# Arduelli.net
KiCad netlist of a schematic drawn in EAGLE
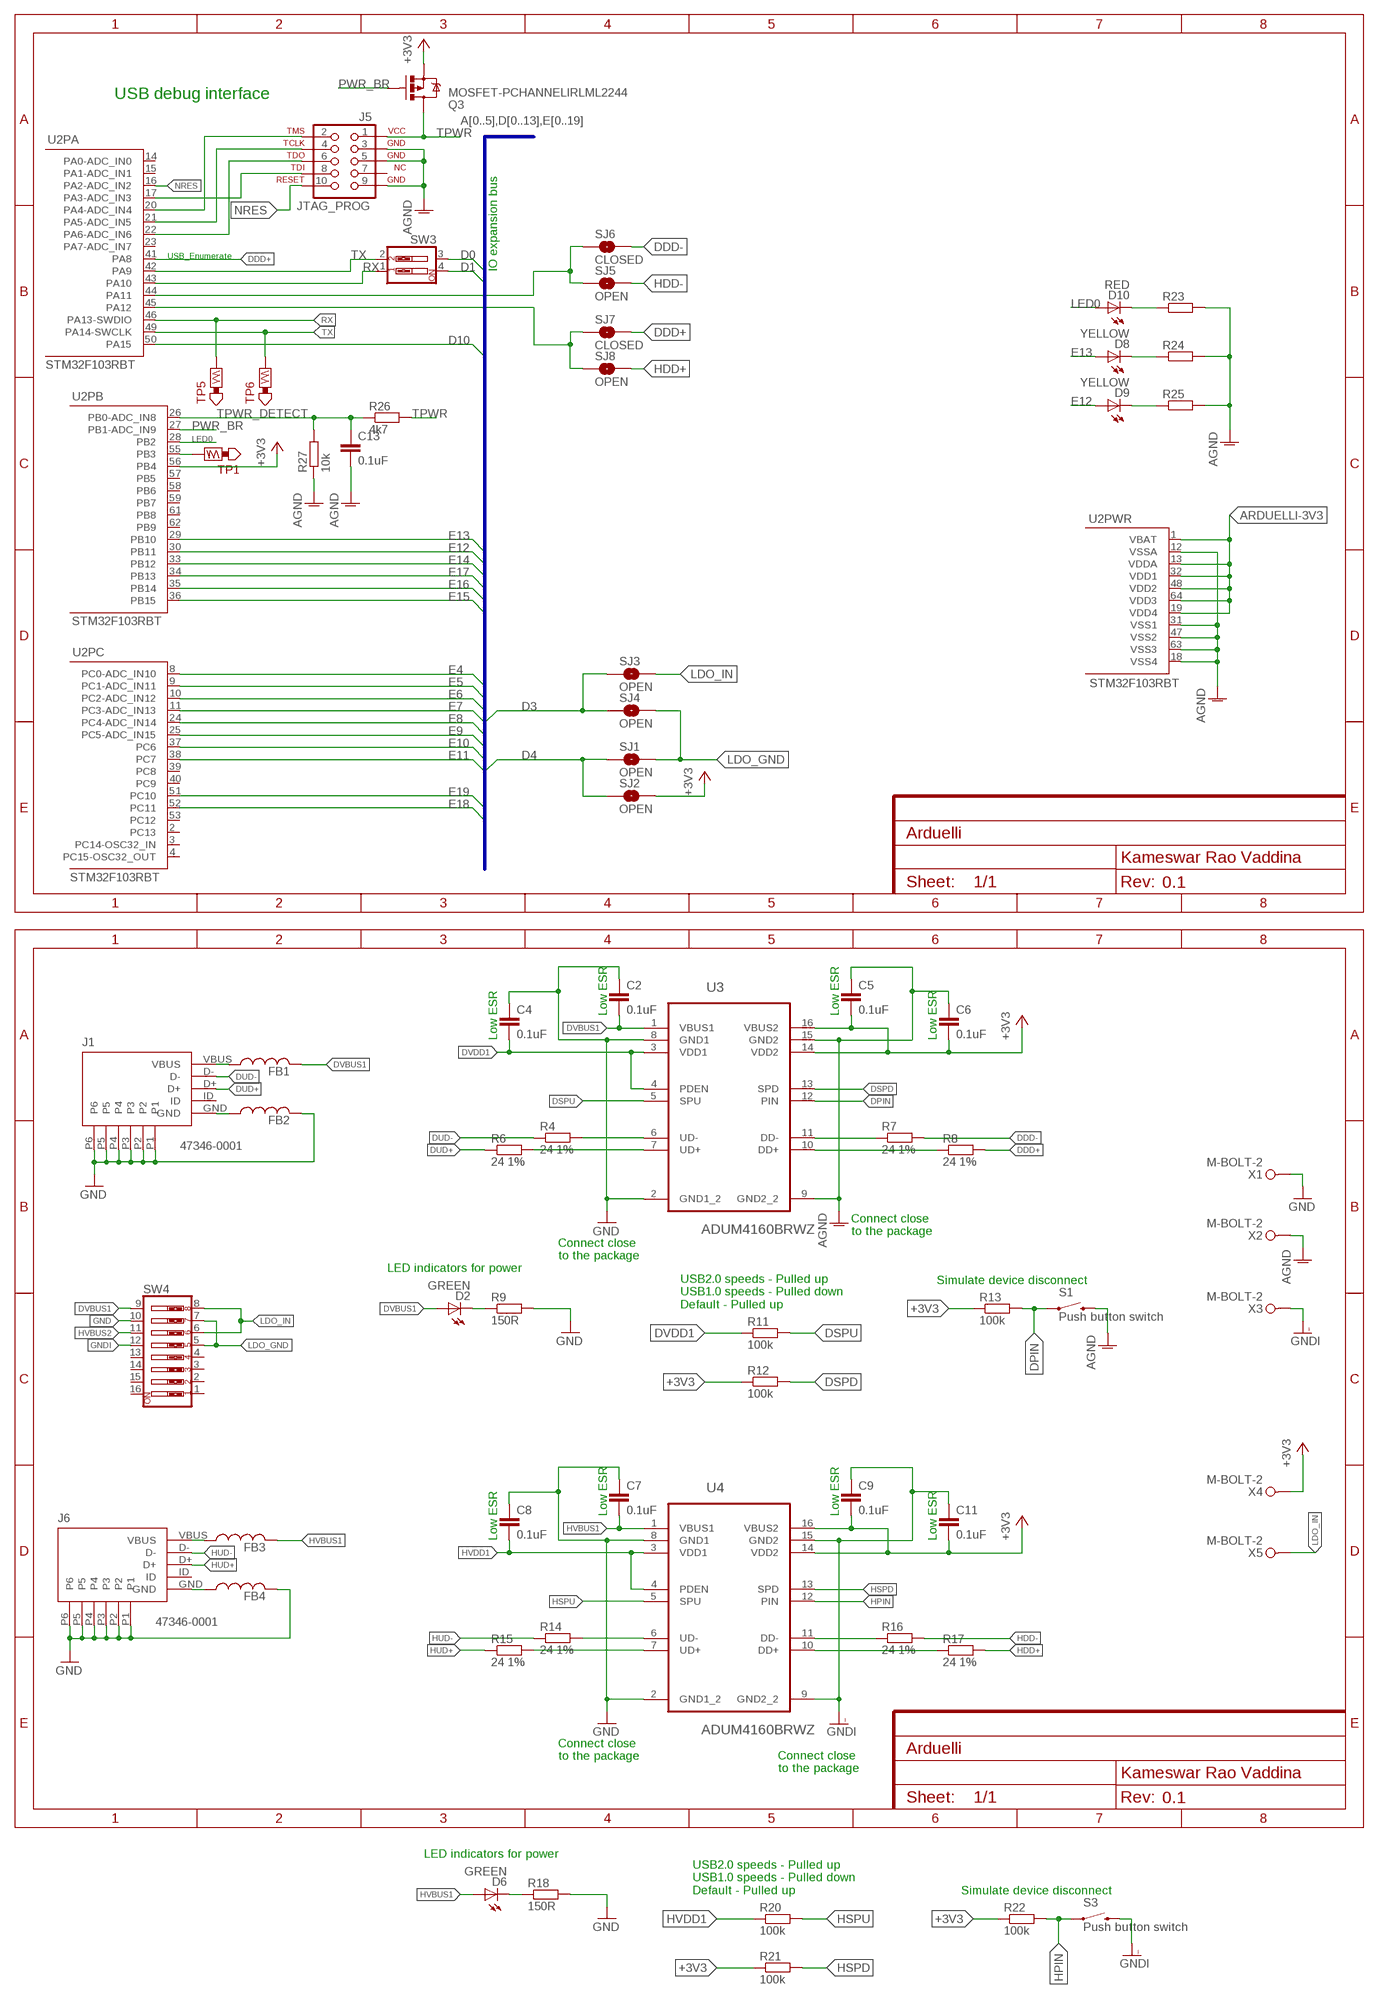
[diagram p0: schematic, sheet 1, part 1 of 2]
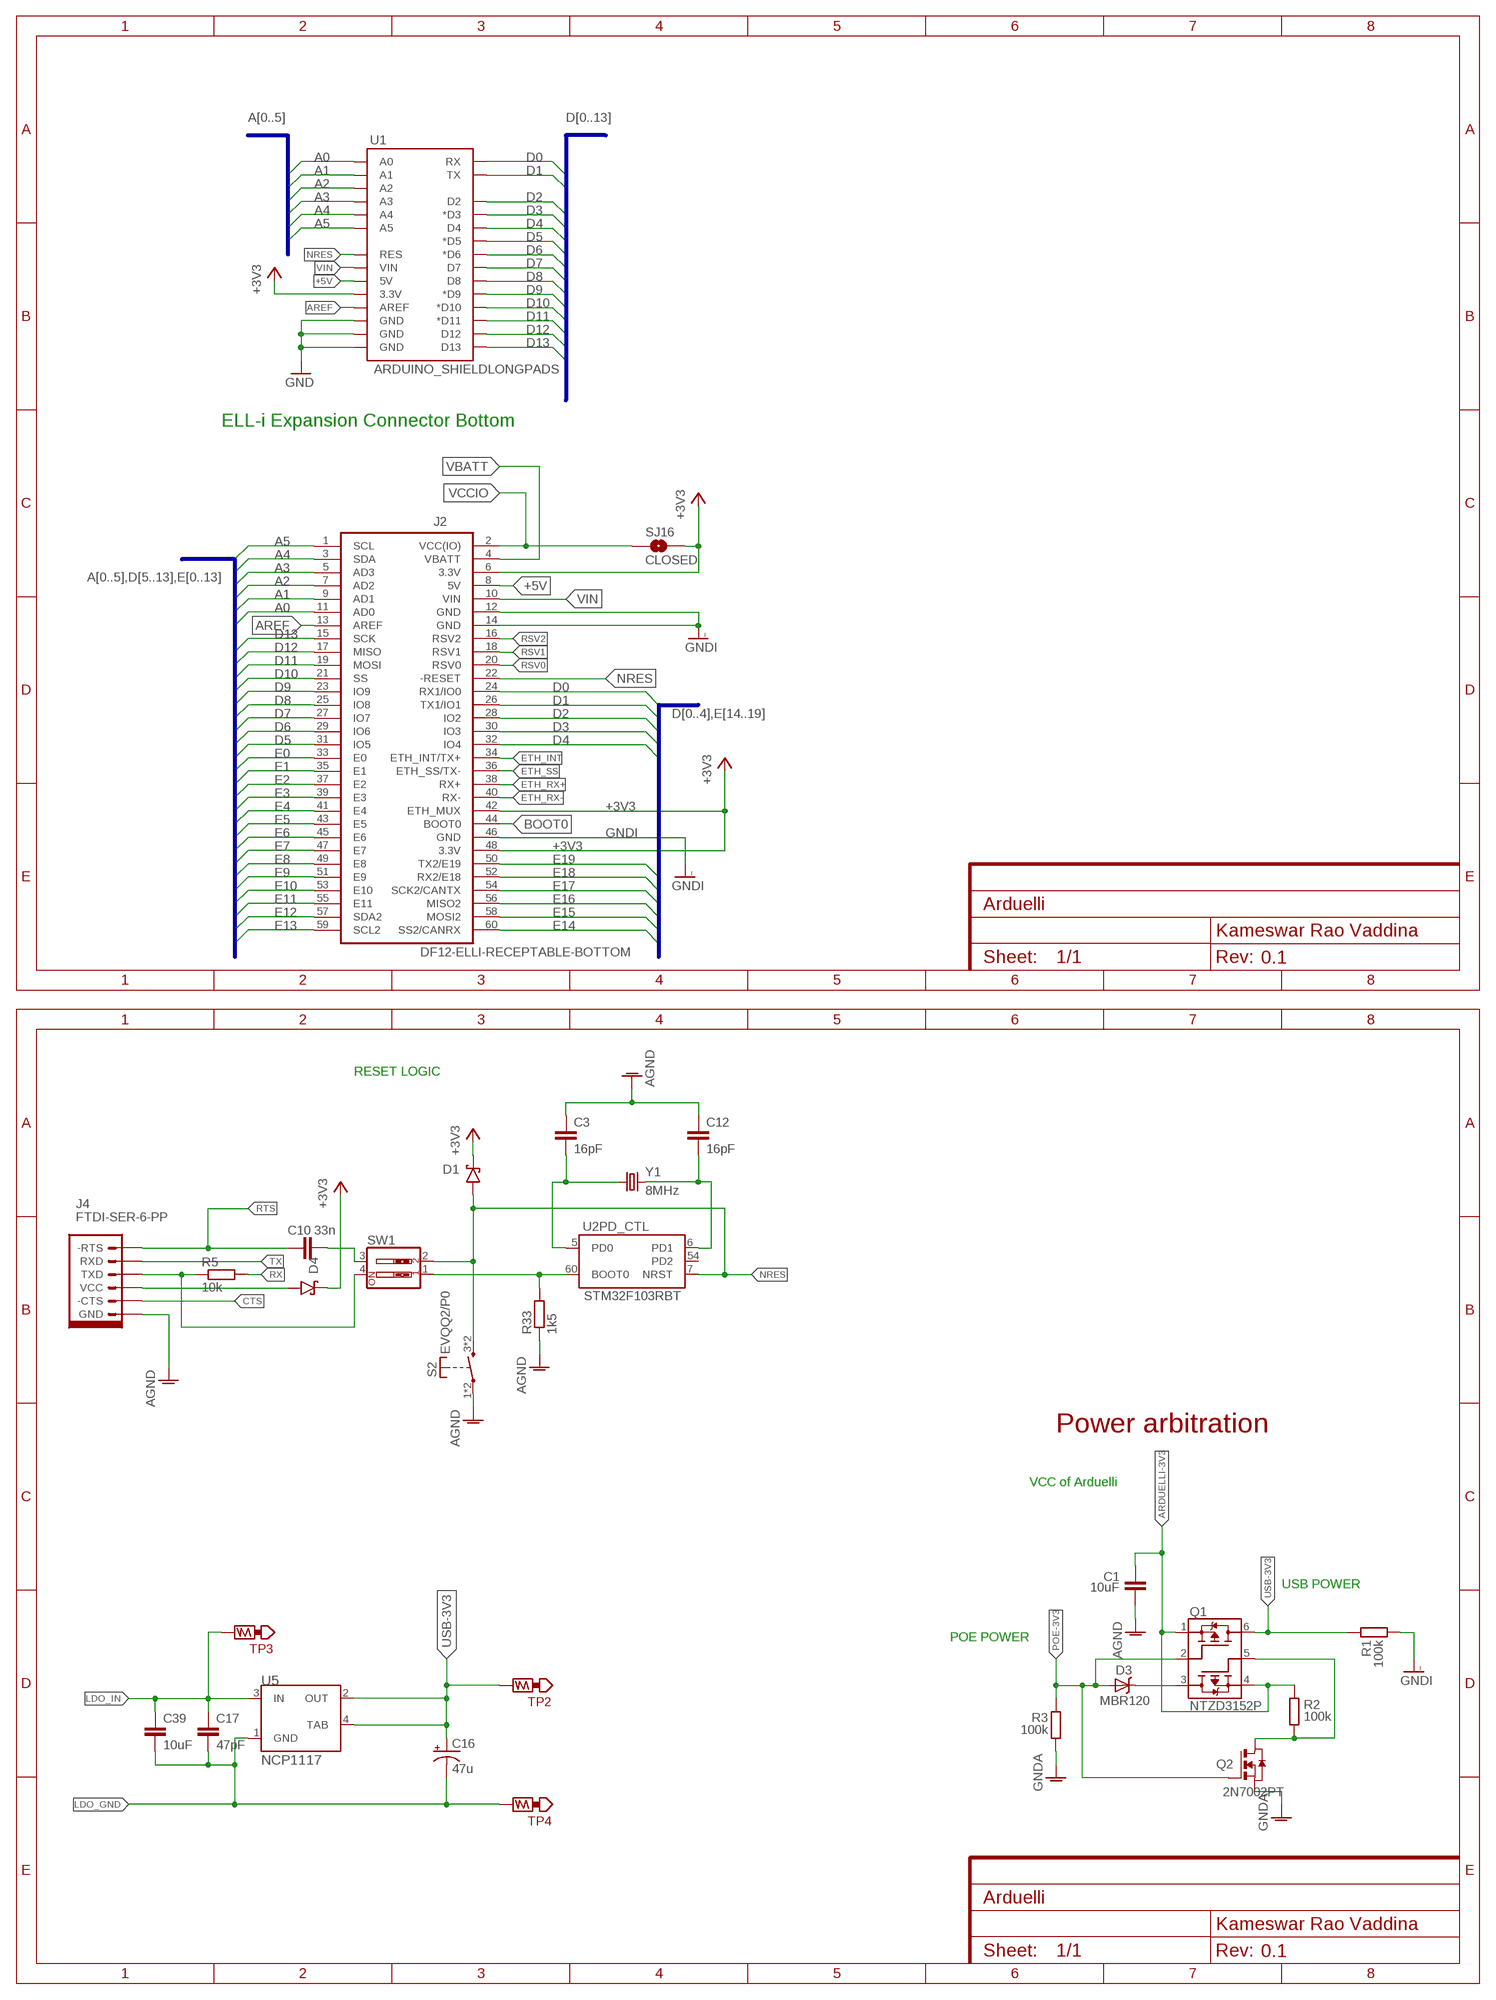
[diagram p1: schematic, sheet 1, part 2 of 2]

(export (version "E")
  (design (tool "Eeschema 10.0.6"))
  (components
    (comp (ref "C1")
      (value "10uF")
      (footprint "eagle-import:C0603")
      (libsource (lib "eagle-import") (part "C0603"))
    )
    (comp (ref "C2")
      (value "0.1uF")
      (footprint "eagle-import:C0402")
      (libsource (lib "eagle-import") (part "C0402"))
    )
    (comp (ref "C3")
      (value "16pF")
      (footprint "eagle-import:C0402")
      (libsource (lib "eagle-import") (part "C0402"))
    )
    (comp (ref "C4")
      (value "0.1uF")
      (footprint "eagle-import:C0402")
      (libsource (lib "eagle-import") (part "C0402"))
    )
    (comp (ref "C5")
      (value "0.1uF")
      (footprint "eagle-import:C0402")
      (libsource (lib "eagle-import") (part "C0402"))
    )
    (comp (ref "C6")
      (value "0.1uF")
      (footprint "eagle-import:C0402")
      (libsource (lib "eagle-import") (part "C0402"))
    )
    (comp (ref "C7")
      (value "0.1uF")
      (footprint "eagle-import:C0402")
      (libsource (lib "eagle-import") (part "C0402"))
    )
    (comp (ref "C8")
      (value "0.1uF")
      (footprint "eagle-import:C0402")
      (libsource (lib "eagle-import") (part "C0402"))
    )
    (comp (ref "C9")
      (value "0.1uF")
      (footprint "eagle-import:C0402")
      (libsource (lib "eagle-import") (part "C0402"))
    )
    (comp (ref "C10")
      (value "33n")
      (footprint "eagle-import:C0402")
      (libsource (lib "eagle-import") (part "C0402"))
    )
    (comp (ref "C11")
      (value "0.1uF")
      (footprint "eagle-import:C0402")
      (libsource (lib "eagle-import") (part "C0402"))
    )
    (comp (ref "C12")
      (value "16pF")
      (footprint "eagle-import:C0402")
      (libsource (lib "eagle-import") (part "C0402"))
    )
    (comp (ref "C13")
      (value "0.1uF")
      (footprint "eagle-import:C0402")
      (libsource (lib "eagle-import") (part "C0402"))
    )
    (comp (ref "C16")
      (value "47u")
      (footprint "eagle-import:CT6032")
      (libsource (lib "eagle-import") (part "CPOL6032"))
    )
    (comp (ref "C17")
      (value "47pF")
      (footprint "eagle-import:C0805")
      (libsource (lib "eagle-import") (part "C0805"))
    )
    (comp (ref "C39")
      (value "10uF")
      (footprint "eagle-import:C0805")
      (libsource (lib "eagle-import") (part "C0805"))
    )
    (comp (ref "D1")
      (value "BAT60J")
      (footprint "eagle-import:SOD323_DIODE")
      (libsource (lib "eagle-import") (part "BAT60J"))
    )
    (comp (ref "D2")
      (value "GREEN")
      (footprint "eagle-import:LED-0603")
      (libsource (lib "eagle-import") (part "LED-GREEN0603"))
    )
    (comp (ref "D3")
      (value "MBR120")
      (footprint "eagle-import:DIODE-B2100")
      (libsource (lib "eagle-import") (part "DIODE-SCHOTTKYB2100"))
    )
    (comp (ref "D4")
      (value "BAT60J")
      (footprint "eagle-import:SOD323_DIODE")
      (libsource (lib "eagle-import") (part "BAT60J"))
    )
    (comp (ref "D6")
      (value "GREEN")
      (footprint "eagle-import:LED-0603")
      (libsource (lib "eagle-import") (part "LED-GREEN0603"))
    )
    (comp (ref "D8")
      (value "YELLOW")
      (footprint "eagle-import:LED-0603")
      (libsource (lib "eagle-import") (part "LED-YELLOW0603"))
    )
    (comp (ref "D9")
      (value "YELLOW")
      (footprint "eagle-import:LED-0603")
      (libsource (lib "eagle-import") (part "LED-YELLOW0603"))
    )
    (comp (ref "D10")
      (value "RED")
      (footprint "eagle-import:LED-0603")
      (libsource (lib "eagle-import") (part "LED-RED0603"))
    )
    (comp (ref "FB1")
      (value "FB1206")
      (footprint "eagle-import:FB1206")
      (libsource (lib "eagle-import") (part "FB1206"))
    )
    (comp (ref "FB2")
      (value "FB1206")
      (footprint "eagle-import:FB1206")
      (libsource (lib "eagle-import") (part "FB1206"))
    )
    (comp (ref "FB3")
      (value "FB1206")
      (footprint "eagle-import:FB1206")
      (libsource (lib "eagle-import") (part "FB1206"))
    )
    (comp (ref "FB4")
      (value "FB1206")
      (footprint "eagle-import:FB1206")
      (libsource (lib "eagle-import") (part "FB1206"))
    )
    (comp (ref "J1")
      (value "47346-0001")
      (footprint "eagle-import:MICRO_USB")
      (fields (field (name "PARTNO") "AS-ITM-00021"))
      (libsource (lib "eagle-import") (part "MICRO-USB"))
    )
    (comp (ref "J2")
      (value "DF12-ELLI-RECEPTABLE-BOTTOM")
      (footprint "eagle-import:DF12-60DS-0.5V")
      (libsource (lib "eagle-import") (part "DF12-ELLI-RECEPTABLE-BOTTOM"))
    )
    (comp (ref "J4")
      (value "FTDI-SER-6-PP")
      (footprint "eagle-import:FTDI-SER-6-SIL")
      (libsource (lib "eagle-import") (part "FTDI-SER-6-PP"))
    )
    (comp (ref "J5")
      (value "JTAG_PROG")
      (footprint "eagle-import:CLP-105-02-X-D")
      (libsource (lib "eagle-import") (part "JTAG_PROG"))
    )
    (comp (ref "J6")
      (value "47346-0001")
      (footprint "eagle-import:MICRO_USB")
      (fields (field (name "PARTNO") "AS-ITM-00021"))
      (libsource (lib "eagle-import") (part "MICRO-USB"))
    )
    (comp (ref "Q1")
      (value "NTZD3152P")
      (footprint "eagle-import:SOT-563")
      (libsource (lib "eagle-import") (part "NTZD3152P"))
    )
    (comp (ref "Q2")
      (value "2N7002PT")
      (footprint "eagle-import:SOT-416")
      (libsource (lib "eagle-import") (part "2N7002PT"))
    )
    (comp (ref "Q3")
      (value "MOSFET-PCHANNELIRLML2244")
      (footprint "eagle-import:SOT23-3")
      (libsource (lib "eagle-import") (part "MOSFET-PCHANNELIRLML2244"))
    )
    (comp (ref "R1")
      (value "100k")
      (footprint "eagle-import:R0402")
      (libsource (lib "eagle-import") (part "R0402"))
    )
    (comp (ref "R2")
      (value "100k")
      (footprint "eagle-import:R0402")
      (libsource (lib "eagle-import") (part "R0402"))
    )
    (comp (ref "R3")
      (value "100k")
      (footprint "eagle-import:R0402")
      (libsource (lib "eagle-import") (part "R0402"))
    )
    (comp (ref "R4")
      (value "24 1%")
      (footprint "eagle-import:R0402")
      (libsource (lib "eagle-import") (part "R0402"))
    )
    (comp (ref "R5")
      (value "10k")
      (footprint "eagle-import:R0402")
      (libsource (lib "eagle-import") (part "R0402"))
    )
    (comp (ref "R6")
      (value "24 1%")
      (footprint "eagle-import:R0402")
      (libsource (lib "eagle-import") (part "R0402"))
    )
    (comp (ref "R7")
      (value "24 1%")
      (footprint "eagle-import:R0402")
      (libsource (lib "eagle-import") (part "R0402"))
    )
    (comp (ref "R8")
      (value "24 1%")
      (footprint "eagle-import:R0402")
      (libsource (lib "eagle-import") (part "R0402"))
    )
    (comp (ref "R9")
      (value "150R")
      (footprint "eagle-import:R0402")
      (libsource (lib "eagle-import") (part "R0402"))
    )
    (comp (ref "R11")
      (value "100k")
      (footprint "eagle-import:R0402")
      (libsource (lib "eagle-import") (part "R0402"))
    )
    (comp (ref "R12")
      (value "100k")
      (footprint "eagle-import:R0402")
      (libsource (lib "eagle-import") (part "R0402"))
    )
    (comp (ref "R13")
      (value "100k")
      (footprint "eagle-import:R0402")
      (libsource (lib "eagle-import") (part "R0402"))
    )
    (comp (ref "R14")
      (value "24 1%")
      (footprint "eagle-import:R0402")
      (libsource (lib "eagle-import") (part "R0402"))
    )
    (comp (ref "R15")
      (value "24 1%")
      (footprint "eagle-import:R0402")
      (libsource (lib "eagle-import") (part "R0402"))
    )
    (comp (ref "R16")
      (value "24 1%")
      (footprint "eagle-import:R0402")
      (libsource (lib "eagle-import") (part "R0402"))
    )
    (comp (ref "R17")
      (value "24 1%")
      (footprint "eagle-import:R0402")
      (libsource (lib "eagle-import") (part "R0402"))
    )
    (comp (ref "R18")
      (value "150R")
      (footprint "eagle-import:R0402")
      (libsource (lib "eagle-import") (part "R0402"))
    )
    (comp (ref "R20")
      (value "100k")
      (footprint "eagle-import:R0402")
      (libsource (lib "eagle-import") (part "R0402"))
    )
    (comp (ref "R21")
      (value "100k")
      (footprint "eagle-import:R0402")
      (libsource (lib "eagle-import") (part "R0402"))
    )
    (comp (ref "R22")
      (value "100k")
      (footprint "eagle-import:R0402")
      (libsource (lib "eagle-import") (part "R0402"))
    )
    (comp (ref "R23")
      (value "R0402")
      (footprint "eagle-import:R0402")
      (libsource (lib "eagle-import") (part "R0402"))
    )
    (comp (ref "R24")
      (value "R0402")
      (footprint "eagle-import:R0402")
      (libsource (lib "eagle-import") (part "R0402"))
    )
    (comp (ref "R25")
      (value "R0402")
      (footprint "eagle-import:R0402")
      (libsource (lib "eagle-import") (part "R0402"))
    )
    (comp (ref "R26")
      (value "4k7")
      (footprint "eagle-import:R0402")
      (libsource (lib "eagle-import") (part "R0402"))
    )
    (comp (ref "R27")
      (value "10k")
      (footprint "eagle-import:R0402")
      (libsource (lib "eagle-import") (part "R0402"))
    )
    (comp (ref "R33")
      (value "1k5")
      (footprint "eagle-import:R0402")
      (libsource (lib "eagle-import") (part "R0402"))
    )
    (comp (ref "S1")
      (value "Push button switch")
      (footprint "eagle-import:TACTILE_SWITCH_SMD")
      (libsource (lib "eagle-import") (part "SWITCH-MOMENTARY-2SMD"))
    )
    (comp (ref "S2")
      (value "EVQQ2/P0")
      (footprint "eagle-import:EVQQ2_P0")
      (libsource (lib "eagle-import") (part "EVQQ2/P0"))
    )
    (comp (ref "S3")
      (value "Push button switch")
      (footprint "eagle-import:TACTILE_SWITCH_SMD")
      (libsource (lib "eagle-import") (part "SWITCH-MOMENTARY-2SMD"))
    )
    (comp (ref "SJ1")
      (value "OPEN")
      (footprint "eagle-import:SJ_2S-NO")
      (libsource (lib "eagle-import") (part "SOLDERJUMPERNO"))
    )
    (comp (ref "SJ2")
      (value "OPEN")
      (footprint "eagle-import:SJ_2S-NO")
      (libsource (lib "eagle-import") (part "SOLDERJUMPERNO"))
    )
    (comp (ref "SJ3")
      (value "OPEN")
      (footprint "eagle-import:SJ_2S-NO")
      (libsource (lib "eagle-import") (part "SOLDERJUMPERNO"))
    )
    (comp (ref "SJ4")
      (value "OPEN")
      (footprint "eagle-import:SJ_2S-NO")
      (libsource (lib "eagle-import") (part "SOLDERJUMPERNO"))
    )
    (comp (ref "SJ5")
      (value "OPEN")
      (footprint "eagle-import:SJ_2S-NO")
      (libsource (lib "eagle-import") (part "SOLDERJUMPERNO"))
    )
    (comp (ref "SJ6")
      (value "CLOSED")
      (footprint "eagle-import:SJ_2S-NO")
      (libsource (lib "eagle-import") (part "SOLDERJUMPERNO"))
    )
    (comp (ref "SJ7")
      (value "CLOSED")
      (footprint "eagle-import:SJ_2S-NO")
      (libsource (lib "eagle-import") (part "SOLDERJUMPERNO"))
    )
    (comp (ref "SJ8")
      (value "OPEN")
      (footprint "eagle-import:SJ_2S-NO")
      (libsource (lib "eagle-import") (part "SOLDERJUMPERNO"))
    )
    (comp (ref "SJ16")
      (value "CLOSED")
      (footprint "eagle-import:SJ_2S-TRACE")
      (libsource (lib "eagle-import") (part "SOLDERJUMPERTRACE"))
    )
    (comp (ref "SW1")
      (value "SW_DIP-2-SMT-HALFSIZE")
      (footprint "eagle-import:DIPSWITCH-02-50MIL")
      (libsource (lib "eagle-import") (part "SW_DIP-2-SMT-HALFSIZE"))
    )
    (comp (ref "SW3")
      (value "SW_DIP-2-SMT-HALFSIZE")
      (footprint "eagle-import:DIPSWITCH-02-50MIL")
      (libsource (lib "eagle-import") (part "SW_DIP-2-SMT-HALFSIZE"))
    )
    (comp (ref "SW4")
      (value "SW_DIP-8-SMT-HALFSIZE")
      (footprint "eagle-import:DIPSWITCH-08-50MIL")
      (libsource (lib "eagle-import") (part "SW_DIP-8-SMT-HALFSIZE"))
    )
    (comp (ref "TP1")
      (value "TEST_POINT-5000")
      (footprint "eagle-import:TP_5021")
      (libsource (lib "eagle-import") (part "TEST_POINT-5000"))
    )
    (comp (ref "TP2")
      (value "TEST_POINT-5021")
      (footprint "eagle-import:TP_5000")
      (libsource (lib "eagle-import") (part "TEST_POINT-5021"))
    )
    (comp (ref "TP3")
      (value "TEST_POINT-5021")
      (footprint "eagle-import:TP_5000")
      (libsource (lib "eagle-import") (part "TEST_POINT-5021"))
    )
    (comp (ref "TP4")
      (value "TEST_POINT-5021")
      (footprint "eagle-import:TP_5000")
      (libsource (lib "eagle-import") (part "TEST_POINT-5021"))
    )
    (comp (ref "TP5")
      (value "TEST_POINT-5000")
      (footprint "eagle-import:TP_5021")
      (libsource (lib "eagle-import") (part "TEST_POINT-5000"))
    )
    (comp (ref "TP6")
      (value "TEST_POINT-5000")
      (footprint "eagle-import:TP_5021")
      (libsource (lib "eagle-import") (part "TEST_POINT-5000"))
    )
    (comp (ref "U1")
      (value "ARDUINO_SHIELDLONGPADS")
      (footprint "eagle-import:DUEMILANOVE_SHIELD_LONGPADS")
      (libsource (lib "eagle-import") (part "ARDUINO_SHIELDLONGPADS"))
    )
    (comp (ref "U2")
      (value "STM32F103RBT")
      (footprint "eagle-import:LQFP64")
      (libsource (lib "eagle-import") (part "STM32F103RTB"))
    )
    (comp (ref "U3")
      (value "ADUM4160BRWZ")
      (footprint "eagle-import:SOIC127P1032X265-16N")
      (libsource (lib "eagle-import") (part "ADUM4160BRWZ"))
    )
    (comp (ref "U4")
      (value "ADUM4160BRWZ")
      (footprint "eagle-import:SOIC127P1032X265-16N")
      (libsource (lib "eagle-import") (part "ADUM4160BRWZ"))
    )
    (comp (ref "U5")
      (value "NCP1117")
      (footprint "eagle-import:SOT223")
      (libsource (lib "eagle-import") (part "NCP1117"))
    )
    (comp (ref "X1")
      (value "M-BOLT-2")
      (footprint "eagle-import:M2-1")
      (libsource (lib "eagle-import") (part "M-BOLT-2"))
    )
    (comp (ref "X2")
      (value "M-BOLT-2")
      (footprint "eagle-import:M2-1")
      (libsource (lib "eagle-import") (part "M-BOLT-2"))
    )
    (comp (ref "X3")
      (value "M-BOLT-2")
      (footprint "eagle-import:M2-1")
      (libsource (lib "eagle-import") (part "M-BOLT-2"))
    )
    (comp (ref "X4")
      (value "M-BOLT-2")
      (footprint "eagle-import:M2-1")
      (libsource (lib "eagle-import") (part "M-BOLT-2"))
    )
    (comp (ref "X5")
      (value "M-BOLT-2")
      (footprint "eagle-import:M2-1")
      (libsource (lib "eagle-import") (part "M-BOLT-2"))
    )
    (comp (ref "Y1")
      (value "8MHz")
      (footprint "eagle-import:CRYSTAL-TXC-7A")
      (libsource (lib "eagle-import") (part "CRYSTALTXC-7A"))
    )
  )
  (nets
    (net (code "1") (name "+3V3") (class "Default")
      (node (ref "C11") (pin "2") (pinfunction "2_2") (pintype "passive"))
      (node (ref "C5") (pin "2") (pinfunction "2_2") (pintype "passive"))
      (node (ref "C6") (pin "2") (pinfunction "2_2") (pintype "passive"))
      (node (ref "C9") (pin "2") (pinfunction "2_2") (pintype "passive"))
      (node (ref "D1") (pin "1") (pinfunction "C_1") (pintype "passive"))
      (node (ref "D4") (pin "1") (pinfunction "C_1") (pintype "passive"))
      (node (ref "J2") (pin "42") (pinfunction "ETH_MUX_42") (pintype "bidirectional"))
      (node (ref "J2") (pin "48") (pinfunction "3.3V_48") (pintype "bidirectional"))
      (node (ref "J2") (pin "6") (pinfunction "3.3V_6") (pintype "power_in"))
      (node (ref "Q3") (pin "2") (pinfunction "S_2") (pintype "passive"))
      (node (ref "R12") (pin "1") (pinfunction "1_1") (pintype "passive"))
      (node (ref "R13") (pin "1") (pinfunction "1_1") (pintype "passive"))
      (node (ref "R21") (pin "1") (pinfunction "1_1") (pintype "passive"))
      (node (ref "R22") (pin "1") (pinfunction "1_1") (pintype "passive"))
      (node (ref "SJ16") (pin "2") (pinfunction "2_2") (pintype "passive"))
      (node (ref "SJ2") (pin "2") (pinfunction "2_2") (pintype "passive"))
      (node (ref "U1") (pin "3.3V") (pinfunction "3.3V_3.3V") (pintype "bidirectional"))
      (node (ref "U2") (pin "56") (pinfunction "PB4_56") (pintype "bidirectional"))
      (node (ref "U3") (pin "14") (pinfunction "VDD2_14") (pintype "power_in"))
      (node (ref "U3") (pin "16") (pinfunction "VBUS2_16") (pintype "power_in"))
      (node (ref "U4") (pin "14") (pinfunction "VDD2_14") (pintype "power_in"))
      (node (ref "U4") (pin "16") (pinfunction "VBUS2_16") (pintype "power_in"))
      (node (ref "X4") (pin "1") (pinfunction "KL1_1") (pintype "passive"))
    )
    (net (code "2") (name "+5V") (class "Default")
      (node (ref "J2") (pin "8") (pinfunction "5V_8") (pintype "power_in"))
      (node (ref "U1") (pin "5V") (pinfunction "5V_5V") (pintype "bidirectional"))
    )
    (net (code "3") (name "/A0") (class "Default")
      (node (ref "J2") (pin "11") (pinfunction "AD0_11") (pintype "passive"))
      (node (ref "U1") (pin "A0") (pinfunction "A0_A0") (pintype "bidirectional"))
    )
    (net (code "4") (name "/A1") (class "Default")
      (node (ref "J2") (pin "9") (pinfunction "AD1_9") (pintype "passive"))
      (node (ref "U1") (pin "A1") (pinfunction "A1_A1") (pintype "bidirectional"))
    )
    (net (code "5") (name "/A2") (class "Default")
      (node (ref "J2") (pin "7") (pinfunction "AD2_7") (pintype "passive"))
      (node (ref "U1") (pin "A2") (pinfunction "A2_A2") (pintype "bidirectional"))
    )
    (net (code "6") (name "/A3") (class "Default")
      (node (ref "J2") (pin "5") (pinfunction "AD3_5") (pintype "passive"))
      (node (ref "U1") (pin "A3") (pinfunction "A3_A3") (pintype "bidirectional"))
    )
    (net (code "7") (name "/A4") (class "Default")
      (node (ref "J2") (pin "3") (pinfunction "SDA_3") (pintype "bidirectional"))
      (node (ref "U1") (pin "A4") (pinfunction "A4_A4") (pintype "bidirectional"))
    )
    (net (code "8") (name "/A5") (class "Default")
      (node (ref "J2") (pin "1") (pinfunction "SCL_1") (pintype "bidirectional"))
      (node (ref "U1") (pin "A5") (pinfunction "A5_A5") (pintype "bidirectional"))
    )
    (net (code "10") (name "/D0") (class "Default")
      (node (ref "J2") (pin "24") (pinfunction "RX1/IO0_24") (pintype "bidirectional"))
      (node (ref "SW3") (pin "3") (pinfunction "3_3") (pintype "passive"))
      (node (ref "U1") (pin "RX") (pinfunction "RX_RX") (pintype "bidirectional"))
    )
    (net (code "11") (name "/D1") (class "Default")
      (node (ref "J2") (pin "26") (pinfunction "TX1/IO1_26") (pintype "bidirectional"))
      (node (ref "SW3") (pin "4") (pinfunction "4_4") (pintype "passive"))
      (node (ref "U1") (pin "TX") (pinfunction "TX_TX") (pintype "bidirectional"))
    )
    (net (code "12") (name "/D2") (class "Default")
      (node (ref "J2") (pin "28") (pinfunction "IO2_28") (pintype "bidirectional"))
      (node (ref "U1") (pin "D2") (pinfunction "D2_D2") (pintype "bidirectional"))
    )
    (net (code "13") (name "/D3") (class "Default")
      (node (ref "J2") (pin "30") (pinfunction "IO3_30") (pintype "bidirectional"))
      (node (ref "SJ3") (pin "1") (pinfunction "1_1") (pintype "passive"))
      (node (ref "SJ4") (pin "1") (pinfunction "1_1") (pintype "passive"))
      (node (ref "U1") (pin "D3") (pinfunction "*D3_D3") (pintype "bidirectional"))
    )
    (net (code "14") (name "/D4") (class "Default")
      (node (ref "J2") (pin "32") (pinfunction "IO4_32") (pintype "bidirectional"))
      (node (ref "SJ1") (pin "1") (pinfunction "1_1") (pintype "passive"))
      (node (ref "SJ2") (pin "1") (pinfunction "1_1") (pintype "passive"))
      (node (ref "U1") (pin "D4") (pinfunction "D4_D4") (pintype "bidirectional"))
    )
    (net (code "15") (name "/D5") (class "Default")
      (node (ref "J2") (pin "31") (pinfunction "IO5_31") (pintype "bidirectional"))
      (node (ref "U1") (pin "D5") (pinfunction "*D5_D5") (pintype "bidirectional"))
    )
    (net (code "16") (name "/D6") (class "Default")
      (node (ref "J2") (pin "29") (pinfunction "IO6_29") (pintype "bidirectional"))
      (node (ref "U1") (pin "D6") (pinfunction "*D6_D6") (pintype "bidirectional"))
    )
    (net (code "17") (name "/D7") (class "Default")
      (node (ref "J2") (pin "27") (pinfunction "IO7_27") (pintype "bidirectional"))
      (node (ref "U1") (pin "D7") (pinfunction "D7_D7") (pintype "bidirectional"))
    )
    (net (code "18") (name "/D8") (class "Default")
      (node (ref "J2") (pin "25") (pinfunction "IO8_25") (pintype "bidirectional"))
      (node (ref "U1") (pin "D8") (pinfunction "D8_D8") (pintype "bidirectional"))
    )
    (net (code "19") (name "/D9") (class "Default")
      (node (ref "J2") (pin "23") (pinfunction "IO9_23") (pintype "bidirectional"))
      (node (ref "U1") (pin "D9") (pinfunction "*D9_D9") (pintype "bidirectional"))
    )
    (net (code "20") (name "/D10") (class "Default")
      (node (ref "J2") (pin "21") (pinfunction "SS_21") (pintype "bidirectional"))
      (node (ref "U1") (pin "D10") (pinfunction "*D10_D10") (pintype "bidirectional"))
      (node (ref "U2") (pin "50") (pinfunction "PA15_50") (pintype "bidirectional"))
    )
    (net (code "21") (name "/D11") (class "Default")
      (node (ref "J2") (pin "19") (pinfunction "MOSI_19") (pintype "bidirectional"))
      (node (ref "U1") (pin "D11") (pinfunction "*D11_D11") (pintype "bidirectional"))
    )
    (net (code "22") (name "/D12") (class "Default")
      (node (ref "J2") (pin "17") (pinfunction "MISO_17") (pintype "bidirectional"))
      (node (ref "U1") (pin "D12") (pinfunction "D12_D12") (pintype "bidirectional"))
    )
    (net (code "23") (name "/D13") (class "Default")
      (node (ref "J2") (pin "15") (pinfunction "SCK_15") (pintype "bidirectional"))
      (node (ref "U1") (pin "D13") (pinfunction "D13_D13") (pintype "bidirectional"))
    )
    (net (code "25") (name "/E0") (class "Default")
      (node (ref "J2") (pin "33") (pinfunction "E0_33") (pintype "bidirectional"))
    )
    (net (code "26") (name "/E1") (class "Default")
      (node (ref "J2") (pin "35") (pinfunction "E1_35") (pintype "bidirectional"))
    )
    (net (code "27") (name "/E2") (class "Default")
      (node (ref "J2") (pin "37") (pinfunction "E2_37") (pintype "bidirectional"))
    )
    (net (code "28") (name "/E3") (class "Default")
      (node (ref "J2") (pin "39") (pinfunction "E3_39") (pintype "bidirectional"))
    )
    (net (code "29") (name "/E4") (class "Default")
      (node (ref "J2") (pin "41") (pinfunction "E4_41") (pintype "bidirectional"))
      (node (ref "U2") (pin "8") (pinfunction "PC0-ADC_IN10_8") (pintype "bidirectional"))
    )
    (net (code "30") (name "/E5") (class "Default")
      (node (ref "J2") (pin "43") (pinfunction "E5_43") (pintype "bidirectional"))
      (node (ref "U2") (pin "9") (pinfunction "PC1-ADC_IN11_9") (pintype "bidirectional"))
    )
    (net (code "31") (name "/E6") (class "Default")
      (node (ref "J2") (pin "45") (pinfunction "E6_45") (pintype "bidirectional"))
      (node (ref "U2") (pin "10") (pinfunction "PC2-ADC_IN12_10") (pintype "bidirectional"))
    )
    (net (code "32") (name "/E7") (class "Default")
      (node (ref "J2") (pin "47") (pinfunction "E7_47") (pintype "bidirectional"))
      (node (ref "U2") (pin "11") (pinfunction "PC3-ADC_IN13_11") (pintype "bidirectional"))
    )
    (net (code "33") (name "/E8") (class "Default")
      (node (ref "J2") (pin "49") (pinfunction "E8_49") (pintype "bidirectional"))
      (node (ref "U2") (pin "24") (pinfunction "PC4-ADC_IN14_24") (pintype "bidirectional"))
    )
    (net (code "34") (name "/E9") (class "Default")
      (node (ref "J2") (pin "51") (pinfunction "E9_51") (pintype "bidirectional"))
      (node (ref "U2") (pin "25") (pinfunction "PC5-ADC_IN15_25") (pintype "bidirectional"))
    )
    (net (code "35") (name "/E10") (class "Default")
      (node (ref "J2") (pin "53") (pinfunction "E10_53") (pintype "bidirectional"))
      (node (ref "U2") (pin "37") (pinfunction "PC6_37") (pintype "bidirectional"))
    )
    (net (code "36") (name "/E11") (class "Default")
      (node (ref "J2") (pin "55") (pinfunction "E11_55") (pintype "bidirectional"))
      (node (ref "U2") (pin "38") (pinfunction "PC7_38") (pintype "bidirectional"))
    )
    (net (code "37") (name "/E12") (class "Default")
      (node (ref "D9") (pin "A") (pinfunction "A_A") (pintype "passive"))
      (node (ref "J2") (pin "57") (pinfunction "SDA2_57") (pintype "bidirectional"))
      (node (ref "U2") (pin "30") (pinfunction "PB11_30") (pintype "bidirectional"))
    )
    (net (code "38") (name "/E13") (class "Default")
      (node (ref "D8") (pin "A") (pinfunction "A_A") (pintype "passive"))
      (node (ref "J2") (pin "59") (pinfunction "SCL2_59") (pintype "bidirectional"))
      (node (ref "U2") (pin "29") (pinfunction "PB10_29") (pintype "bidirectional"))
    )
    (net (code "39") (name "/E14") (class "Default")
      (node (ref "J2") (pin "60") (pinfunction "SS2/CANRX_60") (pintype "bidirectional"))
      (node (ref "U2") (pin "33") (pinfunction "PB12_33") (pintype "bidirectional"))
    )
    (net (code "40") (name "/E15") (class "Default")
      (node (ref "J2") (pin "58") (pinfunction "MOSI2_58") (pintype "bidirectional"))
      (node (ref "U2") (pin "36") (pinfunction "PB15_36") (pintype "bidirectional"))
    )
    (net (code "41") (name "/E16") (class "Default")
      (node (ref "J2") (pin "56") (pinfunction "MISO2_56") (pintype "bidirectional"))
      (node (ref "U2") (pin "35") (pinfunction "PB14_35") (pintype "bidirectional"))
    )
    (net (code "42") (name "/E17") (class "Default")
      (node (ref "J2") (pin "54") (pinfunction "SCK2/CANTX_54") (pintype "bidirectional"))
      (node (ref "U2") (pin "34") (pinfunction "PB13_34") (pintype "bidirectional"))
    )
    (net (code "43") (name "/E18") (class "Default")
      (node (ref "J2") (pin "52") (pinfunction "RX2/E18_52") (pintype "bidirectional"))
      (node (ref "U2") (pin "52") (pinfunction "PC11_52") (pintype "bidirectional"))
    )
    (net (code "44") (name "/E19") (class "Default")
      (node (ref "J2") (pin "50") (pinfunction "TX2/E19_50") (pintype "bidirectional"))
      (node (ref "U2") (pin "51") (pinfunction "PC10_51") (pintype "bidirectional"))
    )
    (net (code "45") (name "/LED0") (class "Default")
      (node (ref "D10") (pin "A") (pinfunction "A_A") (pintype "passive"))
      (node (ref "U2") (pin "28") (pinfunction "PB2_28") (pintype "bidirectional"))
    )
    (net (code "46") (name "/PWR_BR") (class "Default")
      (node (ref "Q3") (pin "1") (pinfunction "G_1") (pintype "passive"))
      (node (ref "U2") (pin "27") (pinfunction "PB1-ADC_IN9_27") (pintype "bidirectional"))
    )
    (net (code "47") (name "/TPWR") (class "Default")
      (node (ref "J5") (pin "1") (pinfunction "1_1") (pintype "power_in"))
      (node (ref "Q3") (pin "3") (pinfunction "D_3") (pintype "passive"))
      (node (ref "R26") (pin "2") (pinfunction "2_2") (pintype "passive"))
    )
    (net (code "48") (name "/TPWR_DETECT") (class "Default")
      (node (ref "C13") (pin "1") (pinfunction "1_1") (pintype "passive"))
      (node (ref "R26") (pin "1") (pinfunction "1_1") (pintype "passive"))
      (node (ref "R27") (pin "2") (pinfunction "2_2") (pintype "passive"))
      (node (ref "U2") (pin "26") (pinfunction "PB0-ADC_IN8_26") (pintype "bidirectional"))
    )
    (net (code "52") (name "AGND") (class "Default")
      (node (ref "C1") (pin "2") (pinfunction "2_2") (pintype "passive"))
      (node (ref "C12") (pin "1") (pinfunction "1_1") (pintype "passive"))
      (node (ref "C13") (pin "2") (pinfunction "2_2") (pintype "passive"))
      (node (ref "C3") (pin "1") (pinfunction "1_1") (pintype "passive"))
      (node (ref "C5") (pin "1") (pinfunction "1_1") (pintype "passive"))
      (node (ref "C6") (pin "1") (pinfunction "1_1") (pintype "passive"))
      (node (ref "J4") (pin "GND") (pinfunction "GND_GND") (pintype "passive"))
      (node (ref "J5") (pin "3") (pinfunction "3_3") (pintype "power_in"))
      (node (ref "J5") (pin "5") (pinfunction "5_5") (pintype "power_in"))
      (node (ref "J5") (pin "9") (pinfunction "9_9") (pintype "power_in"))
      (node (ref "R23") (pin "2") (pinfunction "2_2") (pintype "passive"))
      (node (ref "R24") (pin "2") (pinfunction "2_2") (pintype "passive"))
      (node (ref "R25") (pin "2") (pinfunction "2_2") (pintype "passive"))
      (node (ref "R27") (pin "1") (pinfunction "1_1") (pintype "passive"))
      (node (ref "R33") (pin "1") (pinfunction "1_1") (pintype "passive"))
      (node (ref "S1") (pin "3") (pinfunction "2_3") (pintype "passive"))
      (node (ref "S2") (pin "1") (pinfunction "P_1") (pintype "passive"))
      (node (ref "S2") (pin "2") (pinfunction "P_2") (pintype "passive"))
      (node (ref "U2") (pin "12") (pinfunction "VSSA_12") (pintype "power_in"))
      (node (ref "U2") (pin "18") (pinfunction "VSS4_18") (pintype "power_in"))
      (node (ref "U2") (pin "31") (pinfunction "VSS1_31") (pintype "power_in"))
      (node (ref "U2") (pin "47") (pinfunction "VSS2_47") (pintype "power_in"))
      (node (ref "U2") (pin "63") (pinfunction "VSS3_63") (pintype "power_in"))
      (node (ref "U3") (pin "15") (pinfunction "GND2_15") (pintype "passive"))
      (node (ref "U3") (pin "9") (pinfunction "GND2_2_9") (pintype "passive"))
      (node (ref "X2") (pin "1") (pinfunction "KL1_1") (pintype "passive"))
    )
    (net (code "53") (name "ARDUELLI-3V3") (class "Default")
      (node (ref "C1") (pin "1") (pinfunction "1_1") (pintype "passive"))
      (node (ref "Q1") (pin "1") (pinfunction "S1_1") (pintype "passive"))
      (node (ref "Q1") (pin "4") (pinfunction "S2_4") (pintype "passive"))
      (node (ref "R2") (pin "2") (pinfunction "2_2") (pintype "passive"))
      (node (ref "U2") (pin "1") (pinfunction "VBAT_1") (pintype "power_in"))
      (node (ref "U2") (pin "13") (pinfunction "VDDA_13") (pintype "power_in"))
      (node (ref "U2") (pin "19") (pinfunction "VDD4_19") (pintype "power_in"))
      (node (ref "U2") (pin "32") (pinfunction "VDD1_32") (pintype "power_in"))
      (node (ref "U2") (pin "48") (pinfunction "VDD2_48") (pintype "power_in"))
      (node (ref "U2") (pin "64") (pinfunction "VDD3_64") (pintype "power_in"))
    )
    (net (code "54") (name "AREF") (class "Default")
      (node (ref "J2") (pin "13") (pinfunction "AREF_13") (pintype "passive"))
      (node (ref "U1") (pin "AREF") (pinfunction "AREF_AREF") (pintype "bidirectional"))
    )
    (net (code "55") (name "BOOT0") (class "Default")
      (node (ref "J2") (pin "44") (pinfunction "BOOT0_44") (pintype "bidirectional"))
      (node (ref "R33") (pin "2") (pinfunction "2_2") (pintype "passive"))
      (node (ref "SW1") (pin "1") (pinfunction "1_1") (pintype "passive"))
      (node (ref "U2") (pin "60") (pinfunction "BOOT0_60") (pintype "input"))
    )
    (net (code "56") (name "CTS") (class "Default")
      (node (ref "J4") (pin "-CTS") (pinfunction "-CTS_-CTS") (pintype "passive"))
    )
    (net (code "57") (name "DDD+") (class "Default")
      (node (ref "R8") (pin "2") (pinfunction "2_2") (pintype "passive"))
      (node (ref "SJ7") (pin "1") (pinfunction "1_1") (pintype "passive"))
      (node (ref "SJ7") (pin "2") (pinfunction "2_2") (pintype "passive"))
      (node (ref "SJ8") (pin "1") (pinfunction "1_1") (pintype "passive"))
      (node (ref "U2") (pin "41") (pinfunction "PA8_41") (pintype "bidirectional"))
      (node (ref "U2") (pin "45") (pinfunction "PA12_45") (pintype "bidirectional"))
    )
    (net (code "58") (name "DDD-") (class "Default")
      (node (ref "R7") (pin "2") (pinfunction "2_2") (pintype "passive"))
      (node (ref "SJ5") (pin "1") (pinfunction "1_1") (pintype "passive"))
      (node (ref "SJ6") (pin "1") (pinfunction "1_1") (pintype "passive"))
      (node (ref "SJ6") (pin "2") (pinfunction "2_2") (pintype "passive"))
      (node (ref "U2") (pin "44") (pinfunction "PA11_44") (pintype "bidirectional"))
    )
    (net (code "59") (name "DPIN") (class "Default")
      (node (ref "R13") (pin "2") (pinfunction "2_2") (pintype "passive"))
      (node (ref "S1") (pin "1") (pinfunction "1_1") (pintype "passive"))
      (node (ref "U3") (pin "12") (pinfunction "PIN_12") (pintype "input"))
    )
    (net (code "60") (name "DSPD") (class "Default")
      (node (ref "R12") (pin "2") (pinfunction "2_2") (pintype "passive"))
      (node (ref "U3") (pin "13") (pinfunction "SPD_13") (pintype "input"))
    )
    (net (code "61") (name "DSPU") (class "Default")
      (node (ref "R11") (pin "2") (pinfunction "2_2") (pintype "passive"))
      (node (ref "U3") (pin "5") (pinfunction "SPU_5") (pintype "input"))
    )
    (net (code "62") (name "DUD+") (class "Default")
      (node (ref "J1") (pin "D+") (pinfunction "D+_D+") (pintype "bidirectional"))
      (node (ref "R6") (pin "1") (pinfunction "1_1") (pintype "passive"))
    )
    (net (code "63") (name "DUD-") (class "Default")
      (node (ref "J1") (pin "D-") (pinfunction "D-_D-") (pintype "bidirectional"))
      (node (ref "R4") (pin "1") (pinfunction "1_1") (pintype "passive"))
    )
    (net (code "64") (name "DVBUS1") (class "Default")
      (node (ref "C2") (pin "2") (pinfunction "2_2") (pintype "passive"))
      (node (ref "D2") (pin "A") (pinfunction "A_A") (pintype "passive"))
      (node (ref "FB1") (pin "1") (pinfunction "1_1") (pintype "passive"))
      (node (ref "SW4") (pin "9") (pinfunction "9_9") (pintype "passive"))
      (node (ref "U3") (pin "1") (pinfunction "VBUS1_1") (pintype "power_in"))
    )
    (net (code "65") (name "DVDD1") (class "Default")
      (node (ref "C4") (pin "2") (pinfunction "2_2") (pintype "passive"))
      (node (ref "R11") (pin "1") (pinfunction "1_1") (pintype "passive"))
      (node (ref "U3") (pin "3") (pinfunction "VDD1_3") (pintype "power_in"))
      (node (ref "U3") (pin "4") (pinfunction "PDEN_4") (pintype "input"))
    )
    (net (code "66") (name "ETH_INT") (class "Default")
      (node (ref "J2") (pin "34") (pinfunction "ETH_INT/TX+_34") (pintype "bidirectional"))
    )
    (net (code "67") (name "ETH_RX+") (class "Default")
      (node (ref "J2") (pin "38") (pinfunction "RX+_38") (pintype "bidirectional"))
    )
    (net (code "68") (name "ETH_RX-") (class "Default")
      (node (ref "J2") (pin "40") (pinfunction "RX-_40") (pintype "bidirectional"))
    )
    (net (code "69") (name "ETH_SS") (class "Default")
      (node (ref "J2") (pin "36") (pinfunction "ETH_SS/TX-_36") (pintype "bidirectional"))
    )
    (net (code "70") (name "GND") (class "Default")
      (node (ref "C2") (pin "1") (pinfunction "1_1") (pintype "passive"))
      (node (ref "C4") (pin "1") (pinfunction "1_1") (pintype "passive"))
      (node (ref "C7") (pin "1") (pinfunction "1_1") (pintype "passive"))
      (node (ref "C8") (pin "1") (pinfunction "1_1") (pintype "passive"))
      (node (ref "FB2") (pin "1") (pinfunction "1_1") (pintype "passive"))
      (node (ref "FB4") (pin "1") (pinfunction "1_1") (pintype "passive"))
      (node (ref "J1") (pin "P1") (pinfunction "P1_P1") (pintype "bidirectional"))
      (node (ref "J1") (pin "P2") (pinfunction "P2_P2") (pintype "bidirectional"))
      (node (ref "J1") (pin "P3") (pinfunction "P3_P3") (pintype "bidirectional"))
      (node (ref "J1") (pin "P4") (pinfunction "P4_P4") (pintype "bidirectional"))
      (node (ref "J1") (pin "P5") (pinfunction "P5_P5") (pintype "bidirectional"))
      (node (ref "J1") (pin "P6") (pinfunction "P6_P6") (pintype "bidirectional"))
      (node (ref "J6") (pin "P1") (pinfunction "P1_P1") (pintype "bidirectional"))
      (node (ref "J6") (pin "P2") (pinfunction "P2_P2") (pintype "bidirectional"))
      (node (ref "J6") (pin "P3") (pinfunction "P3_P3") (pintype "bidirectional"))
      (node (ref "J6") (pin "P4") (pinfunction "P4_P4") (pintype "bidirectional"))
      (node (ref "J6") (pin "P5") (pinfunction "P5_P5") (pintype "bidirectional"))
      (node (ref "J6") (pin "P6") (pinfunction "P6_P6") (pintype "bidirectional"))
      (node (ref "R18") (pin "2") (pinfunction "2_2") (pintype "passive"))
      (node (ref "R9") (pin "2") (pinfunction "2_2") (pintype "passive"))
      (node (ref "SW4") (pin "10") (pinfunction "10_10") (pintype "passive"))
      (node (ref "U1") (pin "GND@0") (pinfunction "GND_GND@0") (pintype "bidirectional"))
      (node (ref "U1") (pin "GND@1") (pinfunction "GND_GND@1") (pintype "bidirectional"))
      (node (ref "U1") (pin "GND@2") (pinfunction "GND_GND@2") (pintype "bidirectional"))
      (node (ref "U3") (pin "2") (pinfunction "GND1_2_2") (pintype "passive"))
      (node (ref "U3") (pin "8") (pinfunction "GND1_8") (pintype "passive"))
      (node (ref "U4") (pin "2") (pinfunction "GND1_2_2") (pintype "passive"))
      (node (ref "U4") (pin "8") (pinfunction "GND1_8") (pintype "passive"))
      (node (ref "X1") (pin "1") (pinfunction "KL1_1") (pintype "passive"))
    )
    (net (code "71") (name "GNDA") (class "Default")
      (node (ref "Q2") (pin "3") (pinfunction "S_3") (pintype "passive"))
      (node (ref "R3") (pin "1") (pinfunction "1_1") (pintype "passive"))
    )
    (net (code "72") (name "GNDI") (class "Default")
      (node (ref "C11") (pin "1") (pinfunction "1_1") (pintype "passive"))
      (node (ref "C9") (pin "1") (pinfunction "1_1") (pintype "passive"))
      (node (ref "J2") (pin "12") (pinfunction "GND_12") (pintype "power_in"))
      (node (ref "J2") (pin "14") (pinfunction "GND_14") (pintype "power_in"))
      (node (ref "J2") (pin "46") (pinfunction "GND_46") (pintype "bidirectional"))
      (node (ref "R1") (pin "1") (pinfunction "1_1") (pintype "passive"))
      (node (ref "S3") (pin "3") (pinfunction "2_3") (pintype "passive"))
      (node (ref "SW4") (pin "12") (pinfunction "12_12") (pintype "passive"))
      (node (ref "U4") (pin "15") (pinfunction "GND2_15") (pintype "passive"))
      (node (ref "U4") (pin "9") (pinfunction "GND2_2_9") (pintype "passive"))
      (node (ref "X3") (pin "1") (pinfunction "KL1_1") (pintype "passive"))
    )
    (net (code "73") (name "HDD+") (class "Default")
      (node (ref "R17") (pin "2") (pinfunction "2_2") (pintype "passive"))
      (node (ref "SJ8") (pin "2") (pinfunction "2_2") (pintype "passive"))
    )
    (net (code "74") (name "HDD-") (class "Default")
      (node (ref "R16") (pin "2") (pinfunction "2_2") (pintype "passive"))
      (node (ref "SJ5") (pin "2") (pinfunction "2_2") (pintype "passive"))
    )
    (net (code "75") (name "HPIN") (class "Default")
      (node (ref "R22") (pin "2") (pinfunction "2_2") (pintype "passive"))
      (node (ref "S3") (pin "1") (pinfunction "1_1") (pintype "passive"))
      (node (ref "U4") (pin "12") (pinfunction "PIN_12") (pintype "input"))
    )
    (net (code "76") (name "HSPD") (class "Default")
      (node (ref "R21") (pin "2") (pinfunction "2_2") (pintype "passive"))
      (node (ref "U4") (pin "13") (pinfunction "SPD_13") (pintype "input"))
    )
    (net (code "77") (name "HSPU") (class "Default")
      (node (ref "R20") (pin "2") (pinfunction "2_2") (pintype "passive"))
      (node (ref "U4") (pin "5") (pinfunction "SPU_5") (pintype "input"))
    )
    (net (code "78") (name "HUD+") (class "Default")
      (node (ref "J6") (pin "D+") (pinfunction "D+_D+") (pintype "bidirectional"))
      (node (ref "R15") (pin "1") (pinfunction "1_1") (pintype "passive"))
    )
    (net (code "79") (name "HUD-") (class "Default")
      (node (ref "J6") (pin "D-") (pinfunction "D-_D-") (pintype "bidirectional"))
      (node (ref "R14") (pin "1") (pinfunction "1_1") (pintype "passive"))
    )
    (net (code "80") (name "HVBUS1") (class "Default")
      (node (ref "C7") (pin "2") (pinfunction "2_2") (pintype "passive"))
      (node (ref "D6") (pin "A") (pinfunction "A_A") (pintype "passive"))
      (node (ref "FB3") (pin "1") (pinfunction "1_1") (pintype "passive"))
      (node (ref "U4") (pin "1") (pinfunction "VBUS1_1") (pintype "power_in"))
    )
    (net (code "81") (name "HVBUS2") (class "Default")
      (node (ref "SW4") (pin "11") (pinfunction "11_11") (pintype "passive"))
    )
    (net (code "82") (name "HVDD1") (class "Default")
      (node (ref "C8") (pin "2") (pinfunction "2_2") (pintype "passive"))
      (node (ref "R20") (pin "1") (pinfunction "1_1") (pintype "passive"))
      (node (ref "U4") (pin "3") (pinfunction "VDD1_3") (pintype "power_in"))
      (node (ref "U4") (pin "4") (pinfunction "PDEN_4") (pintype "input"))
    )
    (net (code "83") (name "LDO_GND") (class "Default")
      (node (ref "C16") (pin "P$2") (pinfunction "-_P$2") (pintype "passive"))
      (node (ref "C17") (pin "2") (pinfunction "2_2") (pintype "passive"))
      (node (ref "C39") (pin "2") (pinfunction "2_2") (pintype "passive"))
      (node (ref "SJ1") (pin "2") (pinfunction "2_2") (pintype "passive"))
      (node (ref "SJ4") (pin "2") (pinfunction "2_2") (pintype "passive"))
      (node (ref "SW4") (pin "5") (pinfunction "5_5") (pintype "passive"))
      (node (ref "SW4") (pin "7") (pinfunction "7_7") (pintype "passive"))
      (node (ref "TP4") (pin "P$1") (pinfunction "P$1_P$1") (pintype "passive"))
      (node (ref "U5") (pin "1") (pinfunction "GND_1") (pintype "bidirectional"))
    )
    (net (code "84") (name "LDO_IN") (class "Default")
      (node (ref "C17") (pin "1") (pinfunction "1_1") (pintype "passive"))
      (node (ref "C39") (pin "1") (pinfunction "1_1") (pintype "passive"))
      (node (ref "SJ3") (pin "2") (pinfunction "2_2") (pintype "passive"))
      (node (ref "SW4") (pin "6") (pinfunction "6_6") (pintype "passive"))
      (node (ref "SW4") (pin "8") (pinfunction "8_8") (pintype "passive"))
      (node (ref "TP3") (pin "P$1") (pinfunction "P$1_P$1") (pintype "passive"))
      (node (ref "U5") (pin "3") (pinfunction "IN_3") (pintype "bidirectional"))
      (node (ref "X5") (pin "1") (pinfunction "KL1_1") (pintype "passive"))
    )
    (net (code "85") (name "NRES") (class "Default")
      (node (ref "D1") (pin "2") (pinfunction "A_2") (pintype "passive"))
      (node (ref "J2") (pin "22") (pinfunction "-RESET_22") (pintype "bidirectional"))
      (node (ref "J5") (pin "10") (pinfunction "10_10") (pintype "bidirectional"))
      (node (ref "S2") (pin "3") (pinfunction "S_3") (pintype "passive"))
      (node (ref "S2") (pin "4") (pinfunction "S_4") (pintype "passive"))
      (node (ref "SW1") (pin "2") (pinfunction "2_2") (pintype "passive"))
      (node (ref "U1") (pin "RES") (pinfunction "RES_RES") (pintype "bidirectional"))
      (node (ref "U2") (pin "16") (pinfunction "PA2-ADC_IN2_16") (pintype "bidirectional"))
      (node (ref "U2") (pin "7") (pinfunction "NRST_7") (pintype "bidirectional"))
    )
    (net (code "86") (name "Net-(C10-Pad2)") (class "Default")
      (node (ref "C10") (pin "2") (pinfunction "2_2") (pintype "passive"))
      (node (ref "SW1") (pin "3") (pinfunction "3_3") (pintype "passive"))
    )
    (net (code "87") (name "Net-(D2-PadC)") (class "Default")
      (node (ref "D2") (pin "C") (pinfunction "C_C") (pintype "passive"))
      (node (ref "R9") (pin "1") (pinfunction "1_1") (pintype "passive"))
    )
    (net (code "88") (name "Net-(D4-A)") (class "Default")
      (node (ref "D4") (pin "2") (pinfunction "A_2") (pintype "passive"))
      (node (ref "J4") (pin "VCC") (pinfunction "VCC_VCC") (pintype "passive"))
    )
    (net (code "89") (name "Net-(D6-PadC)") (class "Default")
      (node (ref "D6") (pin "C") (pinfunction "C_C") (pintype "passive"))
      (node (ref "R18") (pin "1") (pinfunction "1_1") (pintype "passive"))
    )
    (net (code "90") (name "Net-(D8-PadC)") (class "Default")
      (node (ref "D8") (pin "C") (pinfunction "C_C") (pintype "passive"))
      (node (ref "R24") (pin "1") (pinfunction "1_1") (pintype "passive"))
    )
    (net (code "91") (name "Net-(D9-PadC)") (class "Default")
      (node (ref "D9") (pin "C") (pinfunction "C_C") (pintype "passive"))
      (node (ref "R25") (pin "1") (pinfunction "1_1") (pintype "passive"))
    )
    (net (code "92") (name "Net-(D10-PadC)") (class "Default")
      (node (ref "D10") (pin "C") (pinfunction "C_C") (pintype "passive"))
      (node (ref "R23") (pin "1") (pinfunction "1_1") (pintype "passive"))
    )
    (net (code "93") (name "Net-(FB1-Pad2)") (class "Default")
      (node (ref "FB1") (pin "2") (pinfunction "2_2") (pintype "passive"))
      (node (ref "J1") (pin "VBUS") (pinfunction "VBUS_VBUS") (pintype "bidirectional"))
    )
    (net (code "94") (name "Net-(FB2-Pad2)") (class "Default")
      (node (ref "FB2") (pin "2") (pinfunction "2_2") (pintype "passive"))
      (node (ref "J1") (pin "GND") (pinfunction "GND_GND") (pintype "bidirectional"))
    )
    (net (code "95") (name "Net-(FB3-Pad2)") (class "Default")
      (node (ref "FB3") (pin "2") (pinfunction "2_2") (pintype "passive"))
      (node (ref "J6") (pin "VBUS") (pinfunction "VBUS_VBUS") (pintype "bidirectional"))
    )
    (net (code "96") (name "Net-(FB4-Pad2)") (class "Default")
      (node (ref "FB4") (pin "2") (pinfunction "2_2") (pintype "passive"))
      (node (ref "J6") (pin "GND") (pinfunction "GND_GND") (pintype "bidirectional"))
    )
    (net (code "97") (name "Net-(J4-PadTXD)") (class "Default")
      (node (ref "J4") (pin "TXD") (pinfunction "TXD_TXD") (pintype "passive"))
      (node (ref "R5") (pin "1") (pinfunction "1_1") (pintype "passive"))
      (node (ref "SW1") (pin "4") (pinfunction "4_4") (pintype "passive"))
    )
    (net (code "98") (name "Net-(Q1-D2)") (class "Default")
      (node (ref "D3") (pin "C") (pinfunction "C_C") (pintype "passive"))
      (node (ref "Q1") (pin "3") (pinfunction "D2_3") (pintype "passive"))
    )
    (net (code "99") (name "Net-(Q1-G2)") (class "Default")
      (node (ref "Q1") (pin "5") (pinfunction "G2_5") (pintype "passive"))
      (node (ref "Q2") (pin "1") (pinfunction "D_1") (pintype "passive"))
      (node (ref "R2") (pin "1") (pinfunction "1_1") (pintype "passive"))
    )
    (net (code "100") (name "Net-(U2A-PA3-ADC_IN3)") (class "Default")
      (node (ref "J5") (pin "8") (pinfunction "8_8") (pintype "bidirectional"))
      (node (ref "U2") (pin "17") (pinfunction "PA3-ADC_IN3_17") (pintype "bidirectional"))
    )
    (net (code "101") (name "Net-(U2A-PA4-ADC_IN4)") (class "Default")
      (node (ref "J5") (pin "2") (pinfunction "2_2") (pintype "bidirectional"))
      (node (ref "U2") (pin "20") (pinfunction "PA4-ADC_IN4_20") (pintype "bidirectional"))
    )
    (net (code "102") (name "Net-(U2A-PA5-ADC_IN5)") (class "Default")
      (node (ref "J5") (pin "4") (pinfunction "4_4") (pintype "bidirectional"))
      (node (ref "U2") (pin "21") (pinfunction "PA5-ADC_IN5_21") (pintype "bidirectional"))
    )
    (net (code "103") (name "Net-(U2A-PA6-ADC_IN6)") (class "Default")
      (node (ref "J5") (pin "6") (pinfunction "6_6") (pintype "bidirectional"))
      (node (ref "U2") (pin "22") (pinfunction "PA6-ADC_IN6_22") (pintype "bidirectional"))
    )
    (net (code "104") (name "Net-(U2B-PB3)") (class "Default")
      (node (ref "TP1") (pin "P$1") (pinfunction "P$1_P$1") (pintype "passive"))
      (node (ref "U2") (pin "55") (pinfunction "PB3_55") (pintype "bidirectional"))
    )
    (net (code "105") (name "Net-(U2D-PD0)") (class "Default")
      (node (ref "C3") (pin "2") (pinfunction "2_2") (pintype "passive"))
      (node (ref "U2") (pin "5") (pinfunction "PD0_5") (pintype "input"))
      (node (ref "Y1") (pin "P$1") (pinfunction "1_P$1") (pintype "passive"))
    )
    (net (code "106") (name "Net-(U2D-PD1)") (class "Default")
      (node (ref "C12") (pin "2") (pinfunction "2_2") (pintype "passive"))
      (node (ref "U2") (pin "6") (pinfunction "PD1_6") (pintype "output"))
      (node (ref "Y1") (pin "P$2") (pinfunction "2_P$2") (pintype "passive"))
    )
    (net (code "107") (name "Net-(U3-DD+)") (class "Default")
      (node (ref "R8") (pin "1") (pinfunction "1_1") (pintype "passive"))
      (node (ref "U3") (pin "10") (pinfunction "DD+_10") (pintype "bidirectional"))
    )
    (net (code "108") (name "Net-(U3-DD-)") (class "Default")
      (node (ref "R7") (pin "1") (pinfunction "1_1") (pintype "passive"))
      (node (ref "U3") (pin "11") (pinfunction "DD-_11") (pintype "bidirectional"))
    )
    (net (code "109") (name "Net-(U3-UD+)") (class "Default")
      (node (ref "R6") (pin "2") (pinfunction "2_2") (pintype "passive"))
      (node (ref "U3") (pin "7") (pinfunction "UD+_7") (pintype "bidirectional"))
    )
    (net (code "110") (name "Net-(U3-UD-)") (class "Default")
      (node (ref "R4") (pin "2") (pinfunction "2_2") (pintype "passive"))
      (node (ref "U3") (pin "6") (pinfunction "UD-_6") (pintype "bidirectional"))
    )
    (net (code "111") (name "Net-(U4-DD+)") (class "Default")
      (node (ref "R17") (pin "1") (pinfunction "1_1") (pintype "passive"))
      (node (ref "U4") (pin "10") (pinfunction "DD+_10") (pintype "bidirectional"))
    )
    (net (code "112") (name "Net-(U4-DD-)") (class "Default")
      (node (ref "R16") (pin "1") (pinfunction "1_1") (pintype "passive"))
      (node (ref "U4") (pin "11") (pinfunction "DD-_11") (pintype "bidirectional"))
    )
    (net (code "113") (name "Net-(U4-UD+)") (class "Default")
      (node (ref "R15") (pin "2") (pinfunction "2_2") (pintype "passive"))
      (node (ref "U4") (pin "7") (pinfunction "UD+_7") (pintype "bidirectional"))
    )
    (net (code "114") (name "Net-(U4-UD-)") (class "Default")
      (node (ref "R14") (pin "2") (pinfunction "2_2") (pintype "passive"))
      (node (ref "U4") (pin "6") (pinfunction "UD-_6") (pintype "bidirectional"))
    )
    (net (code "115") (name "POE-3V3") (class "Default")
      (node (ref "D3") (pin "A") (pinfunction "A_A") (pintype "passive"))
      (node (ref "Q1") (pin "2") (pinfunction "G1_2") (pintype "passive"))
      (node (ref "Q2") (pin "2") (pinfunction "G_2") (pintype "passive"))
      (node (ref "R3") (pin "2") (pinfunction "2_2") (pintype "passive"))
    )
    (net (code "116") (name "RSV0") (class "Default")
      (node (ref "J2") (pin "20") (pinfunction "RSV0_20") (pintype "passive"))
    )
    (net (code "117") (name "RSV1") (class "Default")
      (node (ref "J2") (pin "18") (pinfunction "RSV1_18") (pintype "passive"))
    )
    (net (code "118") (name "RSV2") (class "Default")
      (node (ref "J2") (pin "16") (pinfunction "RSV2_16") (pintype "passive"))
    )
    (net (code "119") (name "RTS") (class "Default")
      (node (ref "C10") (pin "1") (pinfunction "1_1") (pintype "passive"))
      (node (ref "J4") (pin "-RTS") (pinfunction "-RTS_-RTS") (pintype "passive"))
    )
    (net (code "120") (name "RX") (class "Default")
      (node (ref "R5") (pin "2") (pinfunction "2_2") (pintype "passive"))
      (node (ref "SW3") (pin "1") (pinfunction "1_1") (pintype "passive"))
      (node (ref "TP5") (pin "P$1") (pinfunction "P$1_P$1") (pintype "passive"))
      (node (ref "U2") (pin "43") (pinfunction "PA10_43") (pintype "bidirectional"))
      (node (ref "U2") (pin "46") (pinfunction "PA13-SWDIO_46") (pintype "bidirectional"))
    )
    (net (code "121") (name "TX") (class "Default")
      (node (ref "J4") (pin "RXD") (pinfunction "RXD_RXD") (pintype "passive"))
      (node (ref "SW3") (pin "2") (pinfunction "2_2") (pintype "passive"))
      (node (ref "TP6") (pin "P$1") (pinfunction "P$1_P$1") (pintype "passive"))
      (node (ref "U2") (pin "42") (pinfunction "PA9_42") (pintype "bidirectional"))
      (node (ref "U2") (pin "49") (pinfunction "PA14-SWCLK_49") (pintype "bidirectional"))
    )
    (net (code "122") (name "USB-3V3") (class "Default")
      (node (ref "C16") (pin "P$1") (pinfunction "+_P$1") (pintype "passive"))
      (node (ref "Q1") (pin "6") (pinfunction "D1_6") (pintype "passive"))
      (node (ref "R1") (pin "2") (pinfunction "2_2") (pintype "passive"))
      (node (ref "TP2") (pin "P$1") (pinfunction "P$1_P$1") (pintype "passive"))
      (node (ref "U5") (pin "2") (pinfunction "OUT_2") (pintype "bidirectional"))
      (node (ref "U5") (pin "4") (pinfunction "TAB_4") (pintype "bidirectional"))
    )
    (net (code "123") (name "VBATT") (class "Default")
      (node (ref "J2") (pin "4") (pinfunction "VBATT_4") (pintype "power_in"))
    )
    (net (code "124") (name "VCCIO") (class "Default")
      (node (ref "J2") (pin "2") (pinfunction "VCC(IO)_2") (pintype "power_in"))
      (node (ref "SJ16") (pin "1") (pinfunction "1_1") (pintype "passive"))
    )
    (net (code "125") (name "VIN") (class "Default")
      (node (ref "J2") (pin "10") (pinfunction "VIN_10") (pintype "power_in"))
      (node (ref "U1") (pin "VIN") (pinfunction "VIN_VIN") (pintype "bidirectional"))
    )
    (net (code "126") (name "unconnected-(J1-PadID)") (class "Default")
      (node (ref "J1") (pin "ID") (pinfunction "ID_ID") (pintype "bidirectional"))
    )
    (net (code "127") (name "unconnected-(J5-Pad7)") (class "Default")
      (node (ref "J5") (pin "7") (pinfunction "7_7") (pintype "bidirectional"))
    )
    (net (code "128") (name "unconnected-(J6-PadID)") (class "Default")
      (node (ref "J6") (pin "ID") (pinfunction "ID_ID") (pintype "bidirectional"))
    )
    (net (code "129") (name "unconnected-(SW4-Pad1)") (class "Default")
      (node (ref "SW4") (pin "1") (pinfunction "1_1") (pintype "passive"))
    )
    (net (code "130") (name "unconnected-(SW4-Pad2)") (class "Default")
      (node (ref "SW4") (pin "2") (pinfunction "2_2") (pintype "passive"))
    )
    (net (code "131") (name "unconnected-(SW4-Pad3)") (class "Default")
      (node (ref "SW4") (pin "3") (pinfunction "3_3") (pintype "passive"))
    )
    (net (code "132") (name "unconnected-(SW4-Pad4)") (class "Default")
      (node (ref "SW4") (pin "4") (pinfunction "4_4") (pintype "passive"))
    )
    (net (code "133") (name "unconnected-(SW4-Pad13)") (class "Default")
      (node (ref "SW4") (pin "13") (pinfunction "13_13") (pintype "passive"))
    )
    (net (code "134") (name "unconnected-(SW4-Pad14)") (class "Default")
      (node (ref "SW4") (pin "14") (pinfunction "14_14") (pintype "passive"))
    )
    (net (code "135") (name "unconnected-(SW4-Pad15)") (class "Default")
      (node (ref "SW4") (pin "15") (pinfunction "15_15") (pintype "passive"))
    )
    (net (code "136") (name "unconnected-(SW4-Pad16)") (class "Default")
      (node (ref "SW4") (pin "16") (pinfunction "16_16") (pintype "passive"))
    )
    (net (code "137") (name "unconnected-(U2A-PA0-ADC_IN0-Pad14)") (class "Default")
      (node (ref "U2") (pin "14") (pinfunction "PA0-ADC_IN0_14") (pintype "bidirectional"))
    )
    (net (code "138") (name "unconnected-(U2A-PA1-ADC_IN1-Pad15)") (class "Default")
      (node (ref "U2") (pin "15") (pinfunction "PA1-ADC_IN1_15") (pintype "bidirectional"))
    )
    (net (code "139") (name "unconnected-(U2A-PA7-ADC_IN7-Pad23)") (class "Default")
      (node (ref "U2") (pin "23") (pinfunction "PA7-ADC_IN7_23") (pintype "bidirectional"))
    )
    (net (code "140") (name "unconnected-(U2B-PB5-Pad57)") (class "Default")
      (node (ref "U2") (pin "57") (pinfunction "PB5_57") (pintype "bidirectional"))
    )
    (net (code "141") (name "unconnected-(U2B-PB6-Pad58)") (class "Default")
      (node (ref "U2") (pin "58") (pinfunction "PB6_58") (pintype "bidirectional"))
    )
    (net (code "142") (name "unconnected-(U2B-PB7-Pad59)") (class "Default")
      (node (ref "U2") (pin "59") (pinfunction "PB7_59") (pintype "bidirectional"))
    )
    (net (code "143") (name "unconnected-(U2B-PB8-Pad61)") (class "Default")
      (node (ref "U2") (pin "61") (pinfunction "PB8_61") (pintype "bidirectional"))
    )
    (net (code "144") (name "unconnected-(U2B-PB9-Pad62)") (class "Default")
      (node (ref "U2") (pin "62") (pinfunction "PB9_62") (pintype "bidirectional"))
    )
    (net (code "145") (name "unconnected-(U2C-PC8-Pad39)") (class "Default")
      (node (ref "U2") (pin "39") (pinfunction "PC8_39") (pintype "bidirectional"))
    )
    (net (code "146") (name "unconnected-(U2C-PC9-Pad40)") (class "Default")
      (node (ref "U2") (pin "40") (pinfunction "PC9_40") (pintype "bidirectional"))
    )
    (net (code "147") (name "unconnected-(U2C-PC12-Pad53)") (class "Default")
      (node (ref "U2") (pin "53") (pinfunction "PC12_53") (pintype "bidirectional"))
    )
    (net (code "148") (name "unconnected-(U2C-PC13-Pad2)") (class "Default")
      (node (ref "U2") (pin "2") (pinfunction "PC13_2") (pintype "bidirectional"))
    )
    (net (code "149") (name "unconnected-(U2C-PC14-OSC32_IN-Pad3)") (class "Default")
      (node (ref "U2") (pin "3") (pinfunction "PC14-OSC32_IN_3") (pintype "bidirectional"))
    )
    (net (code "150") (name "unconnected-(U2C-PC15-OSC32_OUT-Pad4)") (class "Default")
      (node (ref "U2") (pin "4") (pinfunction "PC15-OSC32_OUT_4") (pintype "bidirectional"))
    )
    (net (code "151") (name "unconnected-(U2D-PD2-Pad54)") (class "Default")
      (node (ref "U2") (pin "54") (pinfunction "PD2_54") (pintype "bidirectional"))
    )
  )
)
